# OCSPI.net
KiCad netlist of a schematic drawn in Altium Designer
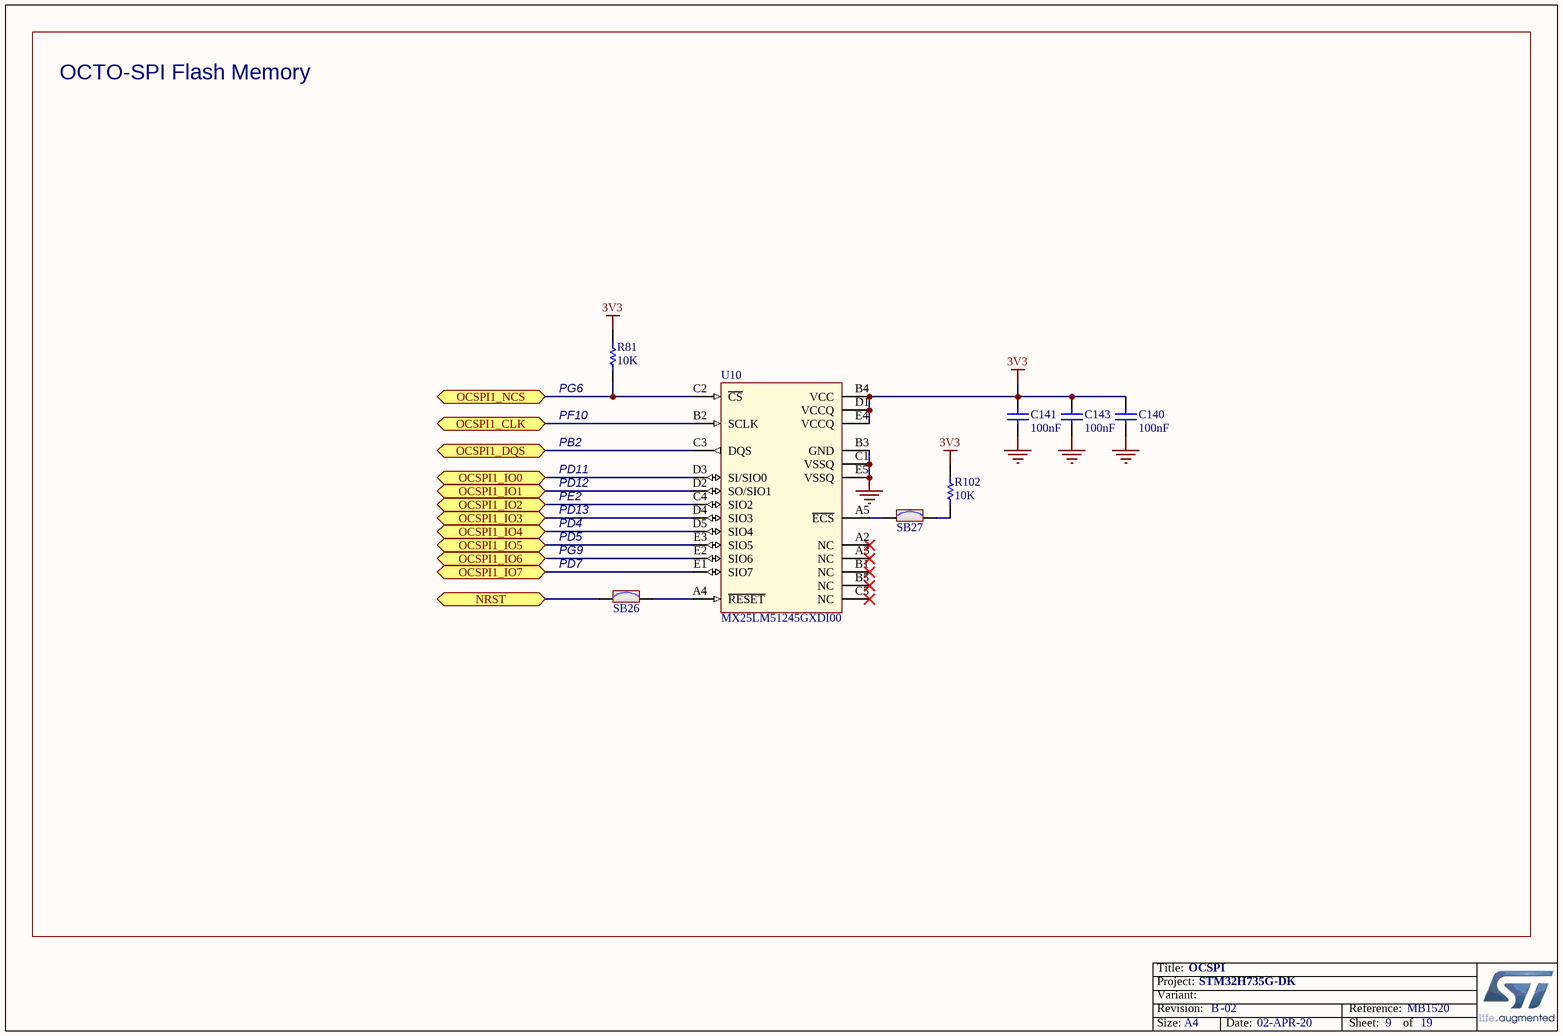
[diagram p0: OCSPI.SchDoc]

(export (version "E")
  (design (tool "Eeschema 10.0.6"))
  (components
    (comp (ref "C140")
      (value "100nF")
      (footprint "C0402")
      (description "Capacitor, MLCC, 100nF, 16V, X7R, 10%, 0402, T=0,5mm")
      (fields
        (field (name "INTERNAL_PART_NUMBER") "MCD-00102")
        (field (name "MANUFACTURER_PART_NUMBER") "CC0402KRX7R7BB104")
        (field (name "PROVIDED_BY") "SUBCO")
      )
      (libsource (lib "MCD_PARTS_database") (part "Capacitor"))
    )
    (comp (ref "C141")
      (value "100nF")
      (footprint "C0402")
      (description "Capacitor, MLCC, 100nF, 16V, X7R, 10%, 0402, T=0,5mm")
      (fields
        (field (name "INTERNAL_PART_NUMBER") "MCD-00102")
        (field (name "MANUFACTURER_PART_NUMBER") "CC0402KRX7R7BB104")
        (field (name "PROVIDED_BY") "SUBCO")
      )
      (libsource (lib "MCD_PARTS_database") (part "Capacitor"))
    )
    (comp (ref "C143")
      (value "100nF")
      (footprint "C0402")
      (description "Capacitor, MLCC, 100nF, 16V, X7R, 10%, 0402, T=0,5mm")
      (fields
        (field (name "INTERNAL_PART_NUMBER") "MCD-00102")
        (field (name "MANUFACTURER_PART_NUMBER") "CC0402KRX7R7BB104")
        (field (name "PROVIDED_BY") "SUBCO")
      )
      (libsource (lib "MCD_PARTS_database") (part "Capacitor"))
    )
    (comp (ref "R81")
      (value "10K")
      (footprint "R0402")
      (description "Resistor,10K,0402,1%,1/16W")
      (fields
        (field (name "INTERNAL_PART_NUMBER") "MCD-00053")
        (field (name "MANUFACTURER_PART_NUMBER") "RC0402FR-0710KL")
        (field (name "PROVIDED_BY") "SUBCO")
      )
      (libsource (lib "MCD_PARTS_database") (part "Resistor"))
    )
    (comp (ref "R102")
      (value "10K")
      (footprint "R0402")
      (description "Resistor,10K,0402,1%,1/16W")
      (fields
        (field (name "INTERNAL_PART_NUMBER") "MCD-00053")
        (field (name "MANUFACTURER_PART_NUMBER") "RC0402FR-0710KL")
        (field (name "PROVIDED_BY") "SUBCO")
      )
      (libsource (lib "MCD_PARTS_database") (part "Resistor"))
    )
    (comp (ref "SB26")
      (value "SB_ON")
      (footprint "SOLDER-BRIDGE_R0603-0R")
      (description "Solder Bridge ON")
      (fields
        (field (name "INTERNAL_PART_NUMBER") "MCD-00071")
        (field (name "MANUFACTURER_PART_NUMBER") "RC0603JR-070RL")
        (field (name "PROVIDED_BY") "SUBCO")
      )
      (libsource (lib "MCD_PARTS_database") (part "SB_ON"))
    )
    (comp (ref "SB27")
      (value "SB_ON")
      (footprint "SOLDER-BRIDGE_R0603-0R")
      (description "Solder Bridge ON")
      (fields
        (field (name "INTERNAL_PART_NUMBER") "MCD-00071")
        (field (name "MANUFACTURER_PART_NUMBER") "RC0603JR-070RL")
        (field (name "PROVIDED_BY") "SUBCO")
      )
      (libsource (lib "MCD_PARTS_database") (part "SB_ON"))
    )
    (comp (ref "U10")
      (value "MX25LM51245GXDI00")
      (footprint "ICC_BGA24_5X5-BALL-ARRAY_6X8_P1")
      (description "Memory,Octo-SPI-NOR,512Mb,2048x16,133MHz,3V,DTR,BGA24, CMOS MXSMIO")
      (fields
        (field (name "INTERNAL_PART_NUMBER") "MCD-00246")
        (field (name "MANUFACTURER") "MACRONIX")
        (field (name "PROVIDED_BY") "SUBCO")
      )
      (libsource (lib "MCD_PARTS_database") (part "MX25LM51245GXDI00"))
    )
  )
  (nets
    (net (code "1") (name "/NRST") (class "Default")
      (node (ref "SB26") (pin "1") (pinfunction "1_1") (pintype "passive"))
    )
    (net (code "2") (name "/OCSPI1_CLK") (class "Default")
      (node (ref "U10") (pin "B2") (pinfunction "SCLK_B2") (pintype "input"))
    )
    (net (code "3") (name "/OCSPI1_DQS") (class "Default")
      (node (ref "U10") (pin "C3") (pinfunction "DQS_C3") (pintype "output"))
    )
    (net (code "4") (name "/OCSPI1_IO0") (class "Default")
      (node (ref "U10") (pin "D3") (pinfunction "SI/SIO0_D3") (pintype "bidirectional"))
    )
    (net (code "5") (name "/OCSPI1_IO1") (class "Default")
      (node (ref "U10") (pin "D2") (pinfunction "SO/SIO1_D2") (pintype "bidirectional"))
    )
    (net (code "6") (name "/OCSPI1_IO2") (class "Default")
      (node (ref "U10") (pin "C4") (pinfunction "SIO2_C4") (pintype "bidirectional"))
    )
    (net (code "7") (name "/OCSPI1_IO3") (class "Default")
      (node (ref "U10") (pin "D4") (pinfunction "SIO3_D4") (pintype "bidirectional"))
    )
    (net (code "8") (name "/OCSPI1_IO4") (class "Default")
      (node (ref "U10") (pin "D5") (pinfunction "SIO4_D5") (pintype "bidirectional"))
    )
    (net (code "9") (name "/OCSPI1_IO5") (class "Default")
      (node (ref "U10") (pin "E3") (pinfunction "SIO5_E3") (pintype "bidirectional"))
    )
    (net (code "10") (name "/OCSPI1_IO6") (class "Default")
      (node (ref "U10") (pin "E2") (pinfunction "SIO6_E2") (pintype "bidirectional"))
    )
    (net (code "11") (name "/OCSPI1_IO7") (class "Default")
      (node (ref "U10") (pin "E1") (pinfunction "SIO7_E1") (pintype "bidirectional"))
    )
    (net (code "12") (name "/OCSPI1_NCS") (class "Default")
      (node (ref "R81") (pin "1") (pinfunction "1_1") (pintype "passive"))
      (node (ref "U10") (pin "C2") (pinfunction "~{CS}_C2") (pintype "input"))
    )
    (net (code "13") (name "3V3") (class "Default")
      (node (ref "C140") (pin "2") (pinfunction "2_2") (pintype "passive"))
      (node (ref "C141") (pin "2") (pinfunction "2_2") (pintype "passive"))
      (node (ref "C143") (pin "2") (pinfunction "2_2") (pintype "passive"))
      (node (ref "R102") (pin "2") (pinfunction "2_2") (pintype "passive"))
      (node (ref "R81") (pin "2") (pinfunction "2_2") (pintype "passive"))
      (node (ref "U10") (pin "B4") (pinfunction "VCC_B4") (pintype "power_in"))
      (node (ref "U10") (pin "D1") (pinfunction "VCCQ_D1") (pintype "power_in"))
      (node (ref "U10") (pin "E4") (pinfunction "VCCQ_E4") (pintype "power_in"))
    )
    (net (code "14") (name "GND") (class "Default")
      (node (ref "C140") (pin "1") (pinfunction "1_1") (pintype "passive"))
      (node (ref "C141") (pin "1") (pinfunction "1_1") (pintype "passive"))
      (node (ref "C143") (pin "1") (pinfunction "1_1") (pintype "passive"))
      (node (ref "U10") (pin "B3") (pinfunction "GND_B3") (pintype "power_in"))
      (node (ref "U10") (pin "C1") (pinfunction "VSSQ_C1") (pintype "power_in"))
      (node (ref "U10") (pin "E5") (pinfunction "VSSQ_E5") (pintype "power_in"))
    )
    (net (code "15") (name "Net-(R102-Pad1)") (class "Default")
      (node (ref "R102") (pin "1") (pinfunction "1_1") (pintype "passive"))
      (node (ref "SB27") (pin "2") (pinfunction "2_2") (pintype "passive"))
    )
    (net (code "16") (name "Net-(U10-~{ECS})") (class "Default")
      (node (ref "SB27") (pin "1") (pinfunction "1_1") (pintype "passive"))
      (node (ref "U10") (pin "A5") (pinfunction "~{ECS}_A5") (pintype "passive"))
    )
    (net (code "17") (name "Net-(U10-~{RESET})") (class "Default")
      (node (ref "SB26") (pin "2") (pinfunction "2_2") (pintype "passive"))
      (node (ref "U10") (pin "A4") (pinfunction "~{RESET}_A4") (pintype "input"))
    )
    (net (code "18") (name "unconnected-(U10-NC-PadA2)") (class "Default")
      (node (ref "U10") (pin "A2") (pinfunction "NC_A2") (pintype "passive+no_connect"))
    )
    (net (code "19") (name "unconnected-(U10-NC-PadA3)") (class "Default")
      (node (ref "U10") (pin "A3") (pinfunction "NC_A3") (pintype "passive+no_connect"))
    )
    (net (code "20") (name "unconnected-(U10-NC-PadB1)") (class "Default")
      (node (ref "U10") (pin "B1") (pinfunction "NC_B1") (pintype "passive+no_connect"))
    )
    (net (code "21") (name "unconnected-(U10-NC-PadB5)") (class "Default")
      (node (ref "U10") (pin "B5") (pinfunction "NC_B5") (pintype "passive+no_connect"))
    )
    (net (code "22") (name "unconnected-(U10-NC-PadC5)") (class "Default")
      (node (ref "U10") (pin "C5") (pinfunction "NC_C5") (pintype "passive+no_connect"))
    )
  )
)
